# design.net
KiCad netlist of a schematic drawn in Altium Designer
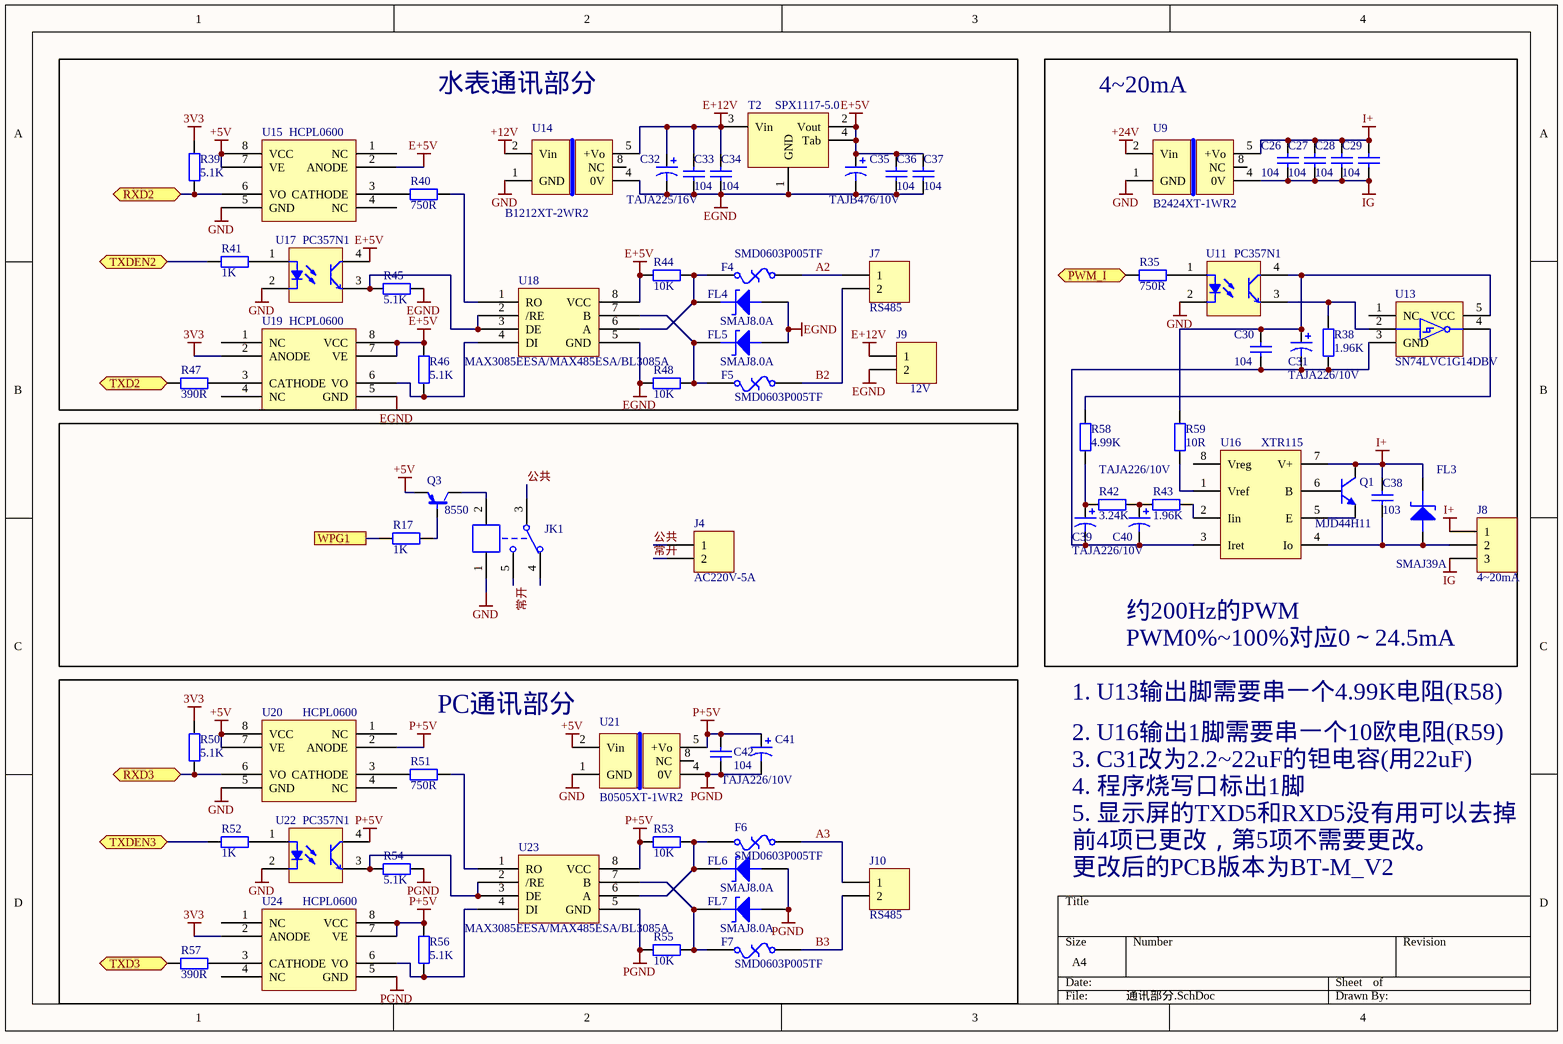
[diagram p0: 通讯部分.SchDoc]

(export (version "E")
  (design (tool "Eeschema 10.0.6"))
  (components
    (comp (ref "C26")
      (value "104")
      (footprint "C 0603_M")
      (description "Capacitor (Semiconductor SIM Model)")
      (fields (field (name "PUBLISHER") "Altium Limited"))
      (libsource (lib "*") (part "Cap Semi"))
    )
    (comp (ref "C27")
      (value "104")
      (footprint "C 0603_M")
      (description "Capacitor (Semiconductor SIM Model)")
      (fields (field (name "PUBLISHER") "Altium Limited"))
      (libsource (lib "*") (part "Cap Semi"))
    )
    (comp (ref "C28")
      (value "104")
      (footprint "C 0603_M")
      (description "Capacitor (Semiconductor SIM Model)")
      (fields (field (name "PUBLISHER") "Altium Limited"))
      (libsource (lib "*") (part "Cap Semi"))
    )
    (comp (ref "C29")
      (value "104")
      (footprint "C 0603_M")
      (description "Capacitor (Semiconductor SIM Model)")
      (fields (field (name "PUBLISHER") "Altium Limited"))
      (libsource (lib "*") (part "Cap Semi"))
    )
    (comp (ref "C30")
      (value "104")
      (footprint "C 0603_M")
      (description "Capacitor (Semiconductor SIM Model)")
      (fields (field (name "PUBLISHER") "Altium Limited"))
      (libsource (lib "*") (part "Cap Semi"))
    )
    (comp (ref "C31")
      (value "TAJA226/10V")
      (footprint "3216")
      (description "Polarized Capacitor (Radial)")
      (fields (field (name "PUBLISHER") "Altium Limited"))
      (libsource (lib "*") (part "Cap Pol1"))
    )
    (comp (ref "C32")
      (value "TAJA225/16V")
      (footprint "3216")
      (description "Polarized Capacitor (Radial)")
      (fields (field (name "PUBLISHER") "Altium Limited"))
      (libsource (lib "*") (part "Cap Pol1"))
    )
    (comp (ref "C33")
      (value "104")
      (footprint "C 0603_M")
      (description "Capacitor (Semiconductor SIM Model)")
      (fields (field (name "PUBLISHER") "Altium Limited"))
      (libsource (lib "*") (part "Cap Semi"))
    )
    (comp (ref "C34")
      (value "104")
      (footprint "C 0603_M")
      (description "Capacitor (Semiconductor SIM Model)")
      (fields (field (name "PUBLISHER") "Altium Limited"))
      (libsource (lib "*") (part "Cap Semi"))
    )
    (comp (ref "C35")
      (value "TAJB476/10V")
      (footprint "3528")
      (description "Polarized Capacitor (Radial)")
      (fields (field (name "PUBLISHER") "Altium Limited"))
      (libsource (lib "*") (part "Cap Pol1"))
    )
    (comp (ref "C36")
      (value "104")
      (footprint "C 0603_M")
      (description "Capacitor (Semiconductor SIM Model)")
      (fields (field (name "PUBLISHER") "Altium Limited"))
      (libsource (lib "*") (part "Cap Semi"))
    )
    (comp (ref "C37")
      (value "104")
      (footprint "C 0603_M")
      (description "Capacitor (Semiconductor SIM Model)")
      (fields (field (name "PUBLISHER") "Altium Limited"))
      (libsource (lib "*") (part "Cap Semi"))
    )
    (comp (ref "C38")
      (value "103")
      (footprint "C 0603_M")
      (description "Capacitor (Semiconductor SIM Model)")
      (fields (field (name "PUBLISHER") "Altium Limited"))
      (libsource (lib "*") (part "Cap Semi"))
    )
    (comp (ref "C39")
      (value "TAJA226/10V")
      (footprint "3216")
      (description "Polarized Capacitor (Radial)")
      (fields (field (name "PUBLISHER") "Altium Limited"))
      (libsource (lib "*") (part "Cap Pol1"))
    )
    (comp (ref "C40")
      (value "TAJA226/10V")
      (footprint "3216")
      (description "Polarized Capacitor (Radial)")
      (fields (field (name "PUBLISHER") "Altium Limited"))
      (libsource (lib "*") (part "Cap Pol1"))
    )
    (comp (ref "C41")
      (value "TAJA226/10V")
      (footprint "3216")
      (description "Polarized Capacitor (Radial)")
      (fields (field (name "PUBLISHER") "Altium Limited"))
      (libsource (lib "*") (part "Cap Pol1"))
    )
    (comp (ref "C42")
      (value "104")
      (footprint "C 0603_M")
      (description "Capacitor (Semiconductor SIM Model)")
      (fields (field (name "PUBLISHER") "Altium Limited"))
      (libsource (lib "*") (part "Cap Semi"))
    )
    (comp (ref "F4")
      (value "SMD0603P005TF")
      (footprint "R 0603_M")
      (description "Thermal Fuse")
      (fields (field (name "PUBLISHER") "50mA"))
      (libsource (lib "communication_Project1") (part "Fuse Thermal"))
    )
    (comp (ref "F5")
      (value "SMD0603P005TF")
      (footprint "R 0603_M")
      (description "Thermal Fuse")
      (fields (field (name "PUBLISHER") "50mA"))
      (libsource (lib "communication_Project1") (part "Fuse Thermal"))
    )
    (comp (ref "F6")
      (value "SMD0603P005TF")
      (footprint "R 0603_M")
      (description "Thermal Fuse")
      (fields (field (name "PUBLISHER") "50mA"))
      (libsource (lib "communication_Project1") (part "Fuse Thermal"))
    )
    (comp (ref "F7")
      (value "SMD0603P005TF")
      (footprint "R 0603_M")
      (description "Thermal Fuse")
      (fields (field (name "PUBLISHER") "50mA"))
      (libsource (lib "communication_Project1") (part "Fuse Thermal"))
    )
    (comp (ref "FL3")
      (value "SMAJ39A")
      (footprint "SMA")
      (description "Zener Diode")
      (libsource (lib "YYL") (part "ZENER2"))
    )
    (comp (ref "FL4")
      (value "SMAJ8.0A")
      (footprint "SMA")
      (description "Zener Diode")
      (libsource (lib "*") (part "ZENER2"))
    )
    (comp (ref "FL5")
      (value "SMAJ8.0A")
      (footprint "SMA")
      (description "Zener Diode")
      (libsource (lib "*") (part "ZENER2"))
    )
    (comp (ref "FL6")
      (value "SMAJ8.0A")
      (footprint "SMA")
      (description "Zener Diode")
      (libsource (lib "*") (part "ZENER2"))
    )
    (comp (ref "FL7")
      (value "SMAJ8.0A")
      (footprint "SMA")
      (description "Zener Diode")
      (libsource (lib "*") (part "ZENER2"))
    )
    (comp (ref "J4")
      (value "AC220V-5A")
      (footprint "KF128-5.08-2P")
      (description "Header, 2-Pin")
      (fields (field (name "PUBLISHER") "Altium Limited"))
      (libsource (lib "Miscellaneous Connectors") (part "Header 2"))
    )
    (comp (ref "J7")
      (value "RS485")
      (footprint "KF128-5.08-2P")
      (description "Header, 2-Pin")
      (fields (field (name "PUBLISHER") "Altium Limited"))
      (libsource (lib "Miscellaneous Connectors") (part "Header 2"))
    )
    (comp (ref "J8")
      (value "4~20mA")
      (footprint "KF128-5.08-3P")
      (description "Header, 3-Pin")
      (fields (field (name "PUBLISHER") "Altium Limited"))
      (libsource (lib "Miscellaneous Connectors") (part "Header 3"))
    )
    (comp (ref "J9")
      (value "12V")
      (footprint "KF128-5.08-2P")
      (description "Header, 2-Pin")
      (fields (field (name "PUBLISHER") "Altium Limited"))
      (libsource (lib "Miscellaneous Connectors") (part "Header 2"))
    )
    (comp (ref "J10")
      (value "RS485")
      (footprint "KF128-5.08-2P")
      (description "Header, 2-Pin")
      (fields (field (name "PUBLISHER") "Altium Limited"))
      (libsource (lib "Miscellaneous Connectors") (part "Header 2"))
    )
    (comp (ref "JK1")
      (value "~")
      (footprint "SRD-C_B")
      (description "5V单路双控继电器")
      (fields (field (name "版权归属") "源创客"))
      (libsource (lib "继电器") (part "SRD-05VDC-SL-C"))
    )
    (comp (ref "Q1")
      (value "MJD44H11")
      (footprint "DPAK")
      (description "NPN Bipolar Transistor")
      (fields (field (name "PUBLISHER") "Altium Limited"))
      (libsource (lib "YYL") (part "MJD44H11"))
    )
    (comp (ref "Q3") (value "8550") (footprint "SOT-23") (libsource (lib "史福祥库") (part "PNP")))
    (comp (ref "R17")
      (value "1K")
      (footprint "R 0603_M")
      (description "Resistor")
      (fields (field (name "PUBLISHER") "Altium Limited"))
      (libsource (lib "*") (part "Res2"))
    )
    (comp (ref "R35")
      (value "750R")
      (footprint "R 0603_M")
      (description "Resistor")
      (fields (field (name "PUBLISHER") "Altium Limited"))
      (libsource (lib "*") (part "Res2"))
    )
    (comp (ref "R38")
      (value "1.96K")
      (footprint "R 0603_M")
      (description "Resistor")
      (fields (field (name "PUBLISHER") "Altium Limited"))
      (libsource (lib "") (part "Res2_3"))
    )
    (comp (ref "R39")
      (value "5.1K")
      (footprint "R 0603_M")
      (description "Resistor")
      (fields (field (name "PUBLISHER") "Altium Limited"))
      (libsource (lib "") (part "Res2_1"))
    )
    (comp (ref "R40")
      (value "750R")
      (footprint "R 0603_M")
      (description "Resistor")
      (fields (field (name "PUBLISHER") "Altium Limited"))
      (libsource (lib "*") (part "Res2"))
    )
    (comp (ref "R41")
      (value "1K")
      (footprint "R 0603_M")
      (description "Resistor")
      (fields (field (name "PUBLISHER") "Altium Limited"))
      (libsource (lib "*") (part "Res2"))
    )
    (comp (ref "R42")
      (value "3.24K")
      (footprint "R 0603_M")
      (description "Resistor")
      (fields (field (name "PUBLISHER") "Altium Limited"))
      (libsource (lib "*") (part "Res2"))
    )
    (comp (ref "R43")
      (value "1.96K")
      (footprint "R 0603_M")
      (description "Resistor")
      (fields (field (name "PUBLISHER") "Altium Limited"))
      (libsource (lib "*") (part "Res2"))
    )
    (comp (ref "R44")
      (value "10K")
      (footprint "R 0603_M")
      (description "Resistor")
      (fields (field (name "PUBLISHER") "Altium Limited"))
      (libsource (lib "") (part "Res2_2"))
    )
    (comp (ref "R45")
      (value "5.1K")
      (footprint "R 0603_M")
      (description "Resistor")
      (fields (field (name "PUBLISHER") "Altium Limited"))
      (libsource (lib "*") (part "Res2"))
    )
    (comp (ref "R46")
      (value "5.1K")
      (footprint "R 0603_M")
      (description "Resistor")
      (fields (field (name "PUBLISHER") "Altium Limited"))
      (libsource (lib "") (part "Res2_1"))
    )
    (comp (ref "R47")
      (value "390R")
      (footprint "R 0603_M")
      (description "Resistor")
      (fields (field (name "PUBLISHER") "Altium Limited"))
      (libsource (lib "*") (part "Res2"))
    )
    (comp (ref "R48")
      (value "10K")
      (footprint "R 0603_M")
      (description "Resistor")
      (fields (field (name "PUBLISHER") "Altium Limited"))
      (libsource (lib "") (part "Res2_2"))
    )
    (comp (ref "R50")
      (value "5.1K")
      (footprint "R 0603_M")
      (description "Resistor")
      (fields (field (name "PUBLISHER") "Altium Limited"))
      (libsource (lib "") (part "Res2_1"))
    )
    (comp (ref "R51")
      (value "750R")
      (footprint "R 0603_M")
      (description "Resistor")
      (fields (field (name "PUBLISHER") "Altium Limited"))
      (libsource (lib "*") (part "Res2"))
    )
    (comp (ref "R52")
      (value "1K")
      (footprint "R 0603_M")
      (description "Resistor")
      (fields (field (name "PUBLISHER") "Altium Limited"))
      (libsource (lib "*") (part "Res2"))
    )
    (comp (ref "R53")
      (value "10K")
      (footprint "R 0603_M")
      (description "Resistor")
      (fields (field (name "PUBLISHER") "Altium Limited"))
      (libsource (lib "") (part "Res2_2"))
    )
    (comp (ref "R54")
      (value "5.1K")
      (footprint "R 0603_M")
      (description "Resistor")
      (fields (field (name "PUBLISHER") "Altium Limited"))
      (libsource (lib "*") (part "Res2"))
    )
    (comp (ref "R55")
      (value "10K")
      (footprint "R 0603_M")
      (description "Resistor")
      (fields (field (name "PUBLISHER") "Altium Limited"))
      (libsource (lib "") (part "Res2_2"))
    )
    (comp (ref "R56")
      (value "5.1K")
      (footprint "R 0603_M")
      (description "Resistor")
      (fields (field (name "PUBLISHER") "Altium Limited"))
      (libsource (lib "") (part "Res2_1"))
    )
    (comp (ref "R57")
      (value "390R")
      (footprint "R 0603_M")
      (description "Resistor")
      (fields (field (name "PUBLISHER") "Altium Limited"))
      (libsource (lib "*") (part "Res2"))
    )
    (comp (ref "R58")
      (value "4.99K")
      (footprint "R 0603_M")
      (description "Resistor")
      (fields (field (name "PUBLISHER") "Altium Limited"))
      (libsource (lib "") (part "Res2_3"))
    )
    (comp (ref "R59")
      (value "10R")
      (footprint "R 0603_M")
      (description "Resistor")
      (fields (field (name "PUBLISHER") "Altium Limited"))
      (libsource (lib "") (part "Res2_3"))
    )
    (comp (ref "T2") (value "SPX1117-5.0") (footprint "SOT-223") (libsource (lib "YYL") (part "1117")))
    (comp (ref "U9") (value "B2424XT-1WR2") (footprint "B_XT-1W") (libsource (lib "YYL") (part "B_XT-1W")))
    (comp (ref "U11") (value "PC357N1") (footprint "PC357") (libsource (lib "YYL") (part "TLP521-1")))
    (comp (ref "U13")
      (value "SN74LVC1G14DBV")
      (footprint "SOT-23-5")
      (libsource (lib "YYL") (part "SN74LVC1G14DBV"))
    )
    (comp (ref "U14") (value "B1212XT-2WR2") (footprint "B_XT-1W") (libsource (lib "YYL") (part "B_XT-1W")))
    (comp (ref "U15") (value "HCPL0600") (footprint "SO-8") (libsource (lib "*") (part "6N137")))
    (comp (ref "U16") (value "XTR115") (footprint "SO-8") (libsource (lib "YYL") (part "XTR115")))
    (comp (ref "U17") (value "PC357N1") (footprint "PC357") (libsource (lib "YYL") (part "TLP521-1")))
    (comp (ref "U18")
      (value "MAX3085EESA/MAX485ESA/BL3085A")
      (footprint "SO-8")
      (libsource (lib "communication_Project1") (part "MAX485"))
    )
    (comp (ref "U19") (value "HCPL0600") (footprint "SO-8") (libsource (lib "") (part "6N137_1")))
    (comp (ref "U20") (value "HCPL0600") (footprint "SO-8") (libsource (lib "*") (part "6N137")))
    (comp (ref "U21") (value "B0505XT-1WR2") (footprint "B_XT-1W") (libsource (lib "YYL") (part "B_XT-1W")))
    (comp (ref "U22") (value "PC357N1") (footprint "PC357") (libsource (lib "YYL") (part "TLP521-1")))
    (comp (ref "U23")
      (value "MAX3085EESA/MAX485ESA/BL3085A")
      (footprint "SO-8")
      (libsource (lib "communication_Project1") (part "MAX485"))
    )
    (comp (ref "U24") (value "HCPL0600") (footprint "SO-8") (libsource (lib "") (part "6N137_1")))
  )
  (nets
    (net (code "1") (name "+5V") (class "Default")
      (node (ref "Q3") (pin "2") (pinfunction "e_2") (pintype "passive"))
      (node (ref "U15") (pin "7") (pinfunction "VE_7") (pintype "passive"))
      (node (ref "U15") (pin "8") (pinfunction "VCC_8") (pintype "passive"))
      (node (ref "U20") (pin "7") (pinfunction "VE_7") (pintype "passive"))
      (node (ref "U20") (pin "8") (pinfunction "VCC_8") (pintype "passive"))
      (node (ref "U21") (pin "2") (pinfunction "Vin_2") (pintype "passive"))
    )
    (net (code "2") (name "+12V") (class "Default")
      (node (ref "U14") (pin "2") (pinfunction "Vin_2") (pintype "passive"))
    )
    (net (code "3") (name "+24V") (class "Default")
      (node (ref "U9") (pin "2") (pinfunction "Vin_2") (pintype "passive"))
    )
    (net (code "4") (name "/A2") (class "Default")
      (node (ref "F4") (pin "1") (pinfunction "1_1") (pintype "passive"))
      (node (ref "J7") (pin "1") (pinfunction "1_1") (pintype "passive"))
    )
    (net (code "5") (name "/A3") (class "Default")
      (node (ref "F6") (pin "1") (pinfunction "1_1") (pintype "passive"))
      (node (ref "J10") (pin "1") (pinfunction "1_1") (pintype "passive"))
    )
    (net (code "6") (name "/B2") (class "Default")
      (node (ref "F5") (pin "1") (pinfunction "1_1") (pintype "passive"))
      (node (ref "J7") (pin "2") (pinfunction "2_2") (pintype "passive"))
    )
    (net (code "7") (name "/B3") (class "Default")
      (node (ref "F7") (pin "1") (pinfunction "1_1") (pintype "passive"))
      (node (ref "J10") (pin "2") (pinfunction "2_2") (pintype "passive"))
    )
    (net (code "8") (name "/PWM_I") (class "Default")
      (node (ref "R35") (pin "1") (pinfunction "1_1") (pintype "passive"))
    )
    (net (code "9") (name "/RXD2") (class "Default")
      (node (ref "R39") (pin "1") (pinfunction "1_1") (pintype "passive"))
      (node (ref "U15") (pin "6") (pinfunction "VO_6") (pintype "passive"))
    )
    (net (code "10") (name "/RXD3") (class "Default")
      (node (ref "R50") (pin "1") (pinfunction "1_1") (pintype "passive"))
      (node (ref "U20") (pin "6") (pinfunction "VO_6") (pintype "passive"))
    )
    (net (code "11") (name "/TXD2") (class "Default")
      (node (ref "R47") (pin "1") (pinfunction "1_1") (pintype "passive"))
    )
    (net (code "12") (name "/TXD3") (class "Default")
      (node (ref "R57") (pin "1") (pinfunction "1_1") (pintype "passive"))
    )
    (net (code "13") (name "/TXDEN2") (class "Default")
      (node (ref "R41") (pin "1") (pinfunction "1_1") (pintype "passive"))
    )
    (net (code "14") (name "/TXDEN3") (class "Default")
      (node (ref "R52") (pin "1") (pinfunction "1_1") (pintype "passive"))
    )
    (net (code "15") (name "/WPG1") (class "Default")
      (node (ref "R17") (pin "1") (pinfunction "1_1") (pintype "passive"))
    )
    (net (code "16") (name "/公共") (class "Default")
      (node (ref "J4") (pin "1") (pinfunction "1_1") (pintype "passive"))
      (node (ref "JK1") (pin "3") (pinfunction "3_3") (pintype "passive"))
    )
    (net (code "17") (name "/常开") (class "Default")
      (node (ref "J4") (pin "2") (pinfunction "2_2") (pintype "passive"))
      (node (ref "JK1") (pin "5") (pinfunction "5_5") (pintype "passive"))
    )
    (net (code "18") (name "3V3") (class "Default")
      (node (ref "R39") (pin "2") (pinfunction "2_2") (pintype "passive"))
      (node (ref "R50") (pin "2") (pinfunction "2_2") (pintype "passive"))
      (node (ref "U19") (pin "2") (pinfunction "ANODE_2") (pintype "passive"))
      (node (ref "U24") (pin "2") (pinfunction "ANODE_2") (pintype "passive"))
    )
    (net (code "19") (name "E+5V") (class "Default")
      (node (ref "C35") (pin "1") (pinfunction "1_1") (pintype "passive"))
      (node (ref "C36") (pin "2") (pinfunction "2_2") (pintype "passive"))
      (node (ref "C37") (pin "2") (pinfunction "2_2") (pintype "passive"))
      (node (ref "R44") (pin "2") (pinfunction "2_2") (pintype "passive"))
      (node (ref "R46") (pin "2") (pinfunction "2_2") (pintype "passive"))
      (node (ref "T2") (pin "2") (pinfunction "Vout_2") (pintype "passive"))
      (node (ref "T2") (pin "4") (pinfunction "Tab_4") (pintype "passive"))
      (node (ref "U15") (pin "2") (pinfunction "ANODE_2") (pintype "passive"))
      (node (ref "U17") (pin "4") (pintype "passive"))
      (node (ref "U18") (pin "8") (pinfunction "VCC_8") (pintype "power_in"))
      (node (ref "U19") (pin "7") (pinfunction "VE_7") (pintype "passive"))
      (node (ref "U19") (pin "8") (pinfunction "VCC_8") (pintype "passive"))
    )
    (net (code "20") (name "E+12V") (class "Default")
      (node (ref "C32") (pin "1") (pinfunction "1_1") (pintype "passive"))
      (node (ref "C33") (pin "2") (pinfunction "2_2") (pintype "passive"))
      (node (ref "C34") (pin "2") (pinfunction "2_2") (pintype "passive"))
      (node (ref "J9") (pin "1") (pinfunction "1_1") (pintype "passive"))
      (node (ref "T2") (pin "3") (pinfunction "Vin_3") (pintype "passive"))
      (node (ref "U14") (pin "5") (pinfunction "+Vo_5") (pintype "passive"))
    )
    (net (code "21") (name "EGND") (class "Default")
      (node (ref "C32") (pin "2") (pinfunction "2_2") (pintype "passive"))
      (node (ref "C33") (pin "1") (pinfunction "1_1") (pintype "passive"))
      (node (ref "C34") (pin "1") (pinfunction "1_1") (pintype "passive"))
      (node (ref "C35") (pin "2") (pinfunction "2_2") (pintype "passive"))
      (node (ref "C36") (pin "1") (pinfunction "1_1") (pintype "passive"))
      (node (ref "C37") (pin "1") (pinfunction "1_1") (pintype "passive"))
      (node (ref "FL4") (pin "1") (pinfunction "A_1") (pintype "passive"))
      (node (ref "FL5") (pin "1") (pinfunction "A_1") (pintype "passive"))
      (node (ref "J9") (pin "2") (pinfunction "2_2") (pintype "passive"))
      (node (ref "R45") (pin "2") (pinfunction "2_2") (pintype "passive"))
      (node (ref "R48") (pin "2") (pinfunction "2_2") (pintype "passive"))
      (node (ref "T2") (pin "1") (pinfunction "GND_1") (pintype "passive"))
      (node (ref "U14") (pin "4") (pinfunction "0V_4") (pintype "passive"))
      (node (ref "U18") (pin "5") (pinfunction "GND_5") (pintype "passive"))
      (node (ref "U19") (pin "5") (pinfunction "GND_5") (pintype "passive"))
    )
    (net (code "22") (name "GND") (class "Default")
      (node (ref "JK1") (pin "1") (pinfunction "1_1") (pintype "passive"))
      (node (ref "U11") (pin "2") (pintype "passive"))
      (node (ref "U14") (pin "1") (pinfunction "GND_1") (pintype "passive"))
      (node (ref "U15") (pin "5") (pinfunction "GND_5") (pintype "passive"))
      (node (ref "U17") (pin "2") (pintype "passive"))
      (node (ref "U20") (pin "5") (pinfunction "GND_5") (pintype "passive"))
      (node (ref "U21") (pin "1") (pinfunction "GND_1") (pintype "passive"))
      (node (ref "U22") (pin "2") (pintype "passive"))
      (node (ref "U9") (pin "1") (pinfunction "GND_1") (pintype "passive"))
    )
    (net (code "23") (name "I+") (class "Default")
      (node (ref "C26") (pin "2") (pinfunction "2_2") (pintype "passive"))
      (node (ref "C27") (pin "2") (pinfunction "2_2") (pintype "passive"))
      (node (ref "C28") (pin "2") (pinfunction "2_2") (pintype "passive"))
      (node (ref "C29") (pin "2") (pinfunction "2_2") (pintype "passive"))
      (node (ref "C38") (pin "2") (pinfunction "2_2") (pintype "passive"))
      (node (ref "FL3") (pin "2") (pinfunction "K_2") (pintype "passive"))
      (node (ref "J8") (pin "1") (pinfunction "1_1") (pintype "passive"))
      (node (ref "Q1") (pin "2") (pinfunction "C_2") (pintype "passive"))
      (node (ref "U16") (pin "7") (pinfunction "V+_7") (pintype "passive"))
      (node (ref "U9") (pin "5") (pinfunction "+Vo_5") (pintype "passive"))
    )
    (net (code "24") (name "IG") (class "Default")
      (node (ref "C26") (pin "1") (pinfunction "1_1") (pintype "passive"))
      (node (ref "C27") (pin "1") (pinfunction "1_1") (pintype "passive"))
      (node (ref "C28") (pin "1") (pinfunction "1_1") (pintype "passive"))
      (node (ref "C29") (pin "1") (pinfunction "1_1") (pintype "passive"))
      (node (ref "J8") (pin "3") (pinfunction "3_3") (pintype "passive"))
      (node (ref "U9") (pin "4") (pinfunction "0V_4") (pintype "passive"))
    )
    (net (code "25") (name "Net-(C39-Pad1)") (class "Default")
      (node (ref "C39") (pin "1") (pinfunction "1_1") (pintype "passive"))
      (node (ref "R42") (pin "1") (pinfunction "1_1") (pintype "passive"))
      (node (ref "R58") (pin "1") (pinfunction "1_1") (pintype "passive"))
    )
    (net (code "26") (name "Net-(C40-Pad1)") (class "Default")
      (node (ref "C40") (pin "1") (pinfunction "1_1") (pintype "passive"))
      (node (ref "R42") (pin "2") (pinfunction "2_2") (pintype "passive"))
      (node (ref "R43") (pin "1") (pinfunction "1_1") (pintype "passive"))
    )
    (net (code "27") (name "Net-(FL3-A)") (class "Default")
      (node (ref "C38") (pin "1") (pinfunction "1_1") (pintype "passive"))
      (node (ref "FL3") (pin "1") (pinfunction "A_1") (pintype "passive"))
      (node (ref "J8") (pin "2") (pinfunction "2_2") (pintype "passive"))
      (node (ref "U16") (pin "4") (pinfunction "Io_4") (pintype "passive"))
    )
    (net (code "28") (name "Net-(FL4-K)") (class "Default")
      (node (ref "F4") (pin "2") (pinfunction "2_2") (pintype "passive"))
      (node (ref "FL4") (pin "2") (pinfunction "K_2") (pintype "passive"))
      (node (ref "R44") (pin "1") (pinfunction "1_1") (pintype "passive"))
      (node (ref "U18") (pin "6") (pinfunction "A_6") (pintype "passive"))
    )
    (net (code "29") (name "Net-(FL5-K)") (class "Default")
      (node (ref "F5") (pin "2") (pinfunction "2_2") (pintype "passive"))
      (node (ref "FL5") (pin "2") (pinfunction "K_2") (pintype "passive"))
      (node (ref "R48") (pin "1") (pinfunction "1_1") (pintype "passive"))
      (node (ref "U18") (pin "7") (pinfunction "B_7") (pintype "passive"))
    )
    (net (code "30") (name "Net-(FL6-K)") (class "Default")
      (node (ref "F6") (pin "2") (pinfunction "2_2") (pintype "passive"))
      (node (ref "FL6") (pin "2") (pinfunction "K_2") (pintype "passive"))
      (node (ref "R53") (pin "1") (pinfunction "1_1") (pintype "passive"))
      (node (ref "U23") (pin "6") (pinfunction "A_6") (pintype "passive"))
    )
    (net (code "31") (name "Net-(FL7-K)") (class "Default")
      (node (ref "F7") (pin "2") (pinfunction "2_2") (pintype "passive"))
      (node (ref "FL7") (pin "2") (pinfunction "K_2") (pintype "passive"))
      (node (ref "R55") (pin "1") (pinfunction "1_1") (pintype "passive"))
      (node (ref "U23") (pin "7") (pinfunction "B_7") (pintype "passive"))
    )
    (net (code "32") (name "Net-(Q1-B)") (class "Default")
      (node (ref "Q1") (pin "1") (pinfunction "B_1") (pintype "passive"))
      (node (ref "U16") (pin "6") (pinfunction "B_6") (pintype "passive"))
    )
    (net (code "33") (name "Net-(Q1-E)") (class "Default")
      (node (ref "Q1") (pin "3") (pinfunction "E_3") (pintype "passive"))
      (node (ref "U16") (pin "5") (pinfunction "E_5") (pintype "passive"))
    )
    (net (code "34") (name "Net-(Q3-b)") (class "Default")
      (node (ref "Q3") (pin "1") (pinfunction "b_1") (pintype "passive"))
      (node (ref "R17") (pin "2") (pinfunction "2_2") (pintype "passive"))
    )
    (net (code "35") (name "Net-(Q3-c)") (class "Default")
      (node (ref "JK1") (pin "2") (pinfunction "2_2") (pintype "passive"))
      (node (ref "Q3") (pin "3") (pinfunction "c_3") (pintype "passive"))
    )
    (net (code "36") (name "Net-(R35-Pad2)") (class "Default")
      (node (ref "R35") (pin "2") (pinfunction "2_2") (pintype "passive"))
      (node (ref "U11") (pin "1") (pintype "passive"))
    )
    (net (code "37") (name "Net-(R38-Pad2)") (class "Default")
      (node (ref "R38") (pin "2") (pinfunction "2_2") (pintype "passive"))
      (node (ref "U11") (pin "3") (pintype "passive"))
      (node (ref "U13") (pin "2") (pintype "passive"))
    )
    (net (code "38") (name "Net-(R41-Pad2)") (class "Default")
      (node (ref "R41") (pin "2") (pinfunction "2_2") (pintype "passive"))
      (node (ref "U17") (pin "1") (pintype "passive"))
    )
    (net (code "39") (name "Net-(R52-Pad2)") (class "Default")
      (node (ref "R52") (pin "2") (pinfunction "2_2") (pintype "passive"))
      (node (ref "U22") (pin "1") (pintype "passive"))
    )
    (net (code "40") (name "Net-(R58-Pad2)") (class "Default")
      (node (ref "R58") (pin "2") (pinfunction "2_2") (pintype "passive"))
      (node (ref "U13") (pin "4") (pintype "passive"))
    )
    (net (code "41") (name "Net-(U13-GND)") (class "Default")
      (node (ref "C30") (pin "1") (pinfunction "1_1") (pintype "passive"))
      (node (ref "C31") (pin "2") (pinfunction "2_2") (pintype "passive"))
      (node (ref "C39") (pin "2") (pinfunction "2_2") (pintype "passive"))
      (node (ref "C40") (pin "2") (pinfunction "2_2") (pintype "passive"))
      (node (ref "R38") (pin "1") (pinfunction "1_1") (pintype "passive"))
      (node (ref "U13") (pin "3") (pinfunction "GND_3") (pintype "passive"))
      (node (ref "U16") (pin "3") (pinfunction "Iret_3") (pintype "passive"))
    )
    (net (code "42") (name "Net-(U13-VCC)") (class "Default")
      (node (ref "C30") (pin "2") (pinfunction "2_2") (pintype "passive"))
      (node (ref "C31") (pin "1") (pinfunction "1_1") (pintype "passive"))
      (node (ref "R59") (pin "2") (pinfunction "2_2") (pintype "passive"))
      (node (ref "U11") (pin "4") (pintype "passive"))
      (node (ref "U13") (pin "5") (pinfunction "VCC_5") (pintype "passive"))
    )
    (net (code "43") (name "Net-(U15-CATHODE)") (class "Default")
      (node (ref "R40") (pin "1") (pinfunction "1_1") (pintype "passive"))
      (node (ref "U15") (pin "3") (pinfunction "CATHODE_3") (pintype "passive"))
    )
    (net (code "44") (name "Net-(U16-Iin)") (class "Default")
      (node (ref "R43") (pin "2") (pinfunction "2_2") (pintype "passive"))
      (node (ref "U16") (pin "2") (pinfunction "Iin_2") (pintype "passive"))
    )
    (net (code "45") (name "Net-(U16-Vref)") (class "Default")
      (node (ref "R59") (pin "1") (pinfunction "1_1") (pintype "passive"))
      (node (ref "U16") (pin "1") (pinfunction "Vref_1") (pintype "passive"))
    )
    (net (code "46") (name "Net-(U18-DE)") (class "Default")
      (node (ref "R45") (pin "1") (pinfunction "1_1") (pintype "passive"))
      (node (ref "U17") (pin "3") (pintype "passive"))
      (node (ref "U18") (pin "2") (pinfunction "/RE_2") (pintype "passive"))
      (node (ref "U18") (pin "3") (pinfunction "DE_3") (pintype "passive"))
    )
    (net (code "47") (name "Net-(U18-DI)") (class "Default")
      (node (ref "R46") (pin "1") (pinfunction "1_1") (pintype "passive"))
      (node (ref "U18") (pin "4") (pinfunction "DI_4") (pintype "passive"))
      (node (ref "U19") (pin "6") (pinfunction "VO_6") (pintype "passive"))
    )
    (net (code "48") (name "Net-(U18-RO)") (class "Default")
      (node (ref "R40") (pin "2") (pinfunction "2_2") (pintype "passive"))
      (node (ref "U18") (pin "1") (pinfunction "RO_1") (pintype "passive"))
    )
    (net (code "49") (name "Net-(U19-CATHODE)") (class "Default")
      (node (ref "R47") (pin "2") (pinfunction "2_2") (pintype "passive"))
      (node (ref "U19") (pin "3") (pinfunction "CATHODE_3") (pintype "passive"))
    )
    (net (code "50") (name "Net-(U20-CATHODE)") (class "Default")
      (node (ref "R51") (pin "1") (pinfunction "1_1") (pintype "passive"))
      (node (ref "U20") (pin "3") (pinfunction "CATHODE_3") (pintype "passive"))
    )
    (net (code "51") (name "Net-(U23-DE)") (class "Default")
      (node (ref "R54") (pin "1") (pinfunction "1_1") (pintype "passive"))
      (node (ref "U22") (pin "3") (pintype "passive"))
      (node (ref "U23") (pin "2") (pinfunction "/RE_2") (pintype "passive"))
      (node (ref "U23") (pin "3") (pinfunction "DE_3") (pintype "passive"))
    )
    (net (code "52") (name "Net-(U23-DI)") (class "Default")
      (node (ref "R56") (pin "1") (pinfunction "1_1") (pintype "passive"))
      (node (ref "U23") (pin "4") (pinfunction "DI_4") (pintype "passive"))
      (node (ref "U24") (pin "6") (pinfunction "VO_6") (pintype "passive"))
    )
    (net (code "53") (name "Net-(U23-RO)") (class "Default")
      (node (ref "R51") (pin "2") (pinfunction "2_2") (pintype "passive"))
      (node (ref "U23") (pin "1") (pinfunction "RO_1") (pintype "passive"))
    )
    (net (code "54") (name "Net-(U24-CATHODE)") (class "Default")
      (node (ref "R57") (pin "2") (pinfunction "2_2") (pintype "passive"))
      (node (ref "U24") (pin "3") (pinfunction "CATHODE_3") (pintype "passive"))
    )
    (net (code "55") (name "P+5V") (class "Default")
      (node (ref "C41") (pin "1") (pinfunction "1_1") (pintype "passive"))
      (node (ref "C42") (pin "2") (pinfunction "2_2") (pintype "passive"))
      (node (ref "R53") (pin "2") (pinfunction "2_2") (pintype "passive"))
      (node (ref "R56") (pin "2") (pinfunction "2_2") (pintype "passive"))
      (node (ref "U20") (pin "2") (pinfunction "ANODE_2") (pintype "passive"))
      (node (ref "U21") (pin "5") (pinfunction "+Vo_5") (pintype "passive"))
      (node (ref "U22") (pin "4") (pintype "passive"))
      (node (ref "U23") (pin "8") (pinfunction "VCC_8") (pintype "power_in"))
      (node (ref "U24") (pin "7") (pinfunction "VE_7") (pintype "passive"))
      (node (ref "U24") (pin "8") (pinfunction "VCC_8") (pintype "passive"))
    )
    (net (code "56") (name "PGND") (class "Default")
      (node (ref "C41") (pin "2") (pinfunction "2_2") (pintype "passive"))
      (node (ref "C42") (pin "1") (pinfunction "1_1") (pintype "passive"))
      (node (ref "FL6") (pin "1") (pinfunction "A_1") (pintype "passive"))
      (node (ref "FL7") (pin "1") (pinfunction "A_1") (pintype "passive"))
      (node (ref "R54") (pin "2") (pinfunction "2_2") (pintype "passive"))
      (node (ref "R55") (pin "2") (pinfunction "2_2") (pintype "passive"))
      (node (ref "U21") (pin "4") (pinfunction "0V_4") (pintype "passive"))
      (node (ref "U23") (pin "5") (pinfunction "GND_5") (pintype "passive"))
      (node (ref "U24") (pin "5") (pinfunction "GND_5") (pintype "passive"))
    )
    (net (code "57") (name "unconnected-(JK1-Pad4)") (class "Default")
      (node (ref "JK1") (pin "4") (pinfunction "4_4") (pintype "passive"))
    )
    (net (code "58") (name "unconnected-(U9-NC-Pad8)") (class "Default")
      (node (ref "U9") (pin "8") (pinfunction "NC_8") (pintype "passive"))
    )
    (net (code "59") (name "unconnected-(U13-NC-Pad1)") (class "Default")
      (node (ref "U13") (pin "1") (pinfunction "NC_1") (pintype "passive"))
    )
    (net (code "60") (name "unconnected-(U14-NC-Pad8)") (class "Default")
      (node (ref "U14") (pin "8") (pinfunction "NC_8") (pintype "passive"))
    )
    (net (code "61") (name "unconnected-(U15-NC-Pad1)") (class "Default")
      (node (ref "U15") (pin "1") (pinfunction "NC_1") (pintype "passive"))
    )
    (net (code "62") (name "unconnected-(U15-NC-Pad4)") (class "Default")
      (node (ref "U15") (pin "4") (pinfunction "NC_4") (pintype "passive"))
    )
    (net (code "63") (name "unconnected-(U16-Vreg-Pad8)") (class "Default")
      (node (ref "U16") (pin "8") (pinfunction "Vreg_8") (pintype "passive"))
    )
    (net (code "64") (name "unconnected-(U19-NC-Pad1)") (class "Default")
      (node (ref "U19") (pin "1") (pinfunction "NC_1") (pintype "passive"))
    )
    (net (code "65") (name "unconnected-(U19-NC-Pad4)") (class "Default")
      (node (ref "U19") (pin "4") (pinfunction "NC_4") (pintype "passive"))
    )
    (net (code "66") (name "unconnected-(U20-NC-Pad1)") (class "Default")
      (node (ref "U20") (pin "1") (pinfunction "NC_1") (pintype "passive"))
    )
    (net (code "67") (name "unconnected-(U20-NC-Pad4)") (class "Default")
      (node (ref "U20") (pin "4") (pinfunction "NC_4") (pintype "passive"))
    )
    (net (code "68") (name "unconnected-(U21-NC-Pad8)") (class "Default")
      (node (ref "U21") (pin "8") (pinfunction "NC_8") (pintype "passive"))
    )
    (net (code "69") (name "unconnected-(U24-NC-Pad1)") (class "Default")
      (node (ref "U24") (pin "1") (pinfunction "NC_1") (pintype "passive"))
    )
    (net (code "70") (name "unconnected-(U24-NC-Pad4)") (class "Default")
      (node (ref "U24") (pin "4") (pinfunction "NC_4") (pintype "passive"))
    )
  )
)
